# BMWifi.net
KiCad netlist of a schematic drawn in EAGLE
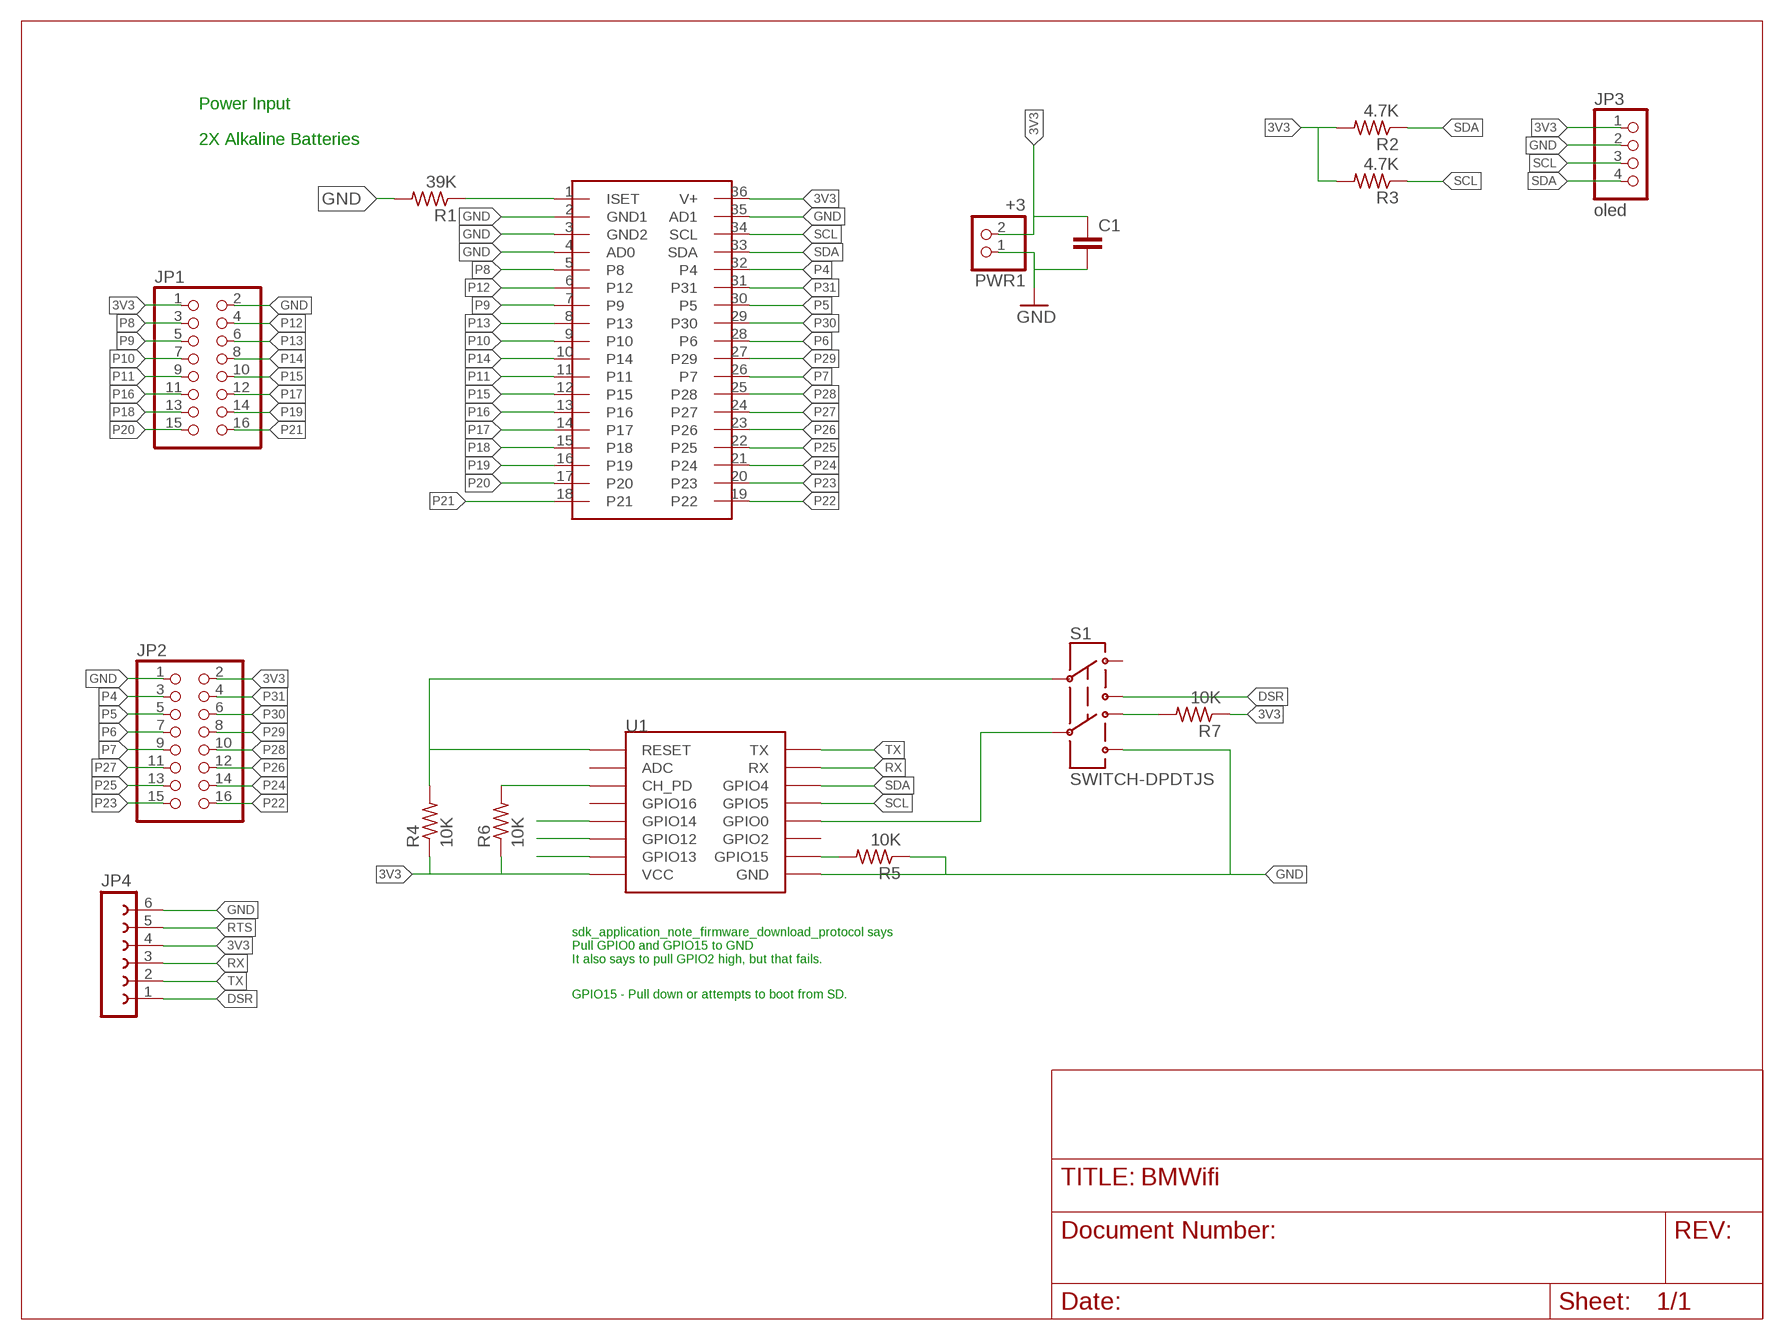
[diagram p0: schematic, sheet 1]

(export (version "E")
  (design (tool "Eeschema 10.0.6"))
  (components
    (comp (ref "C1")
      (value "C2.5/2")
      (footprint "eagle-import:C2.5-2")
      (libsource (lib "eagle-import") (part "C2.5/2"))
    )
    (comp (ref "JP1")
      (value "PINHD-2X8")
      (footprint "eagle-import:2X08")
      (libsource (lib "eagle-import") (part "PINHD-2X8"))
    )
    (comp (ref "JP2")
      (value "PINHD-2X8")
      (footprint "eagle-import:2X08")
      (libsource (lib "eagle-import") (part "PINHD-2X8"))
    )
    (comp (ref "JP3")
      (value "oled")
      (footprint "eagle-import:1X04")
      (libsource (lib "eagle-import") (part "PINHD-1X4"))
    )
    (comp (ref "JP4")
      (value "FE06W")
      (footprint "eagle-import:FE06W")
      (libsource (lib "eagle-import") (part "FE06W"))
    )
    (comp (ref "PWR1")
      (value "+3")
      (footprint "eagle-import:1X02")
      (libsource (lib "eagle-import") (part "PINHD-1X2"))
    )
    (comp (ref "R1")
      (value "39K")
      (footprint "eagle-import:M1206")
      (libsource (lib "eagle-import") (part "R-US_M1206"))
    )
    (comp (ref "R2")
      (value "4.7K")
      (footprint "eagle-import:M1206")
      (libsource (lib "eagle-import") (part "R-US_M1206"))
    )
    (comp (ref "R3")
      (value "4.7K")
      (footprint "eagle-import:M1206")
      (libsource (lib "eagle-import") (part "R-US_M1206"))
    )
    (comp (ref "R4")
      (value "10K")
      (footprint "eagle-import:M1206")
      (libsource (lib "eagle-import") (part "R-US_M1206"))
    )
    (comp (ref "R5")
      (value "10K")
      (footprint "eagle-import:M1206")
      (libsource (lib "eagle-import") (part "R-US_M1206"))
    )
    (comp (ref "R6")
      (value "10K")
      (footprint "eagle-import:M1206")
      (libsource (lib "eagle-import") (part "R-US_M1206"))
    )
    (comp (ref "R7")
      (value "10K")
      (footprint "eagle-import:M1206")
      (libsource (lib "eagle-import") (part "R-US_M1206"))
    )
    (comp (ref "S1")
      (value "SWITCH-DPDTJS")
      (footprint "eagle-import:JS202011CQN")
      (libsource (lib "eagle-import") (part "SWITCH-DPDTJS"))
    )
    (comp (ref "U$1")
      (value "MAX6956")
      (footprint "eagle-import:SSOP36")
      (libsource (lib "eagle-import") (part "MAX6956"))
    )
    (comp (ref "U1")
      (value "ESP12")
      (footprint "eagle-import:ESP12")
      (libsource (lib "eagle-import") (part "ESP12"))
    )
  )
  (nets
    (net (code "1") (name "3V3") (class "Default")
      (node (ref "C1") (pin "1") (pinfunction "1_1") (pintype "passive"))
      (node (ref "JP1") (pin "1") (pinfunction "1_1") (pintype "passive"))
      (node (ref "JP2") (pin "2") (pinfunction "2_2") (pintype "passive"))
      (node (ref "JP3") (pin "1") (pinfunction "1_1") (pintype "passive"))
      (node (ref "JP4") (pin "4") (pinfunction "4_4") (pintype "passive"))
      (node (ref "PWR1") (pin "2") (pinfunction "2_2") (pintype "passive"))
      (node (ref "R2") (pin "2") (pinfunction "2_2") (pintype "passive"))
      (node (ref "R3") (pin "2") (pinfunction "2_2") (pintype "passive"))
      (node (ref "R4") (pin "1") (pinfunction "1_1") (pintype "passive"))
      (node (ref "R6") (pin "1") (pinfunction "1_1") (pintype "passive"))
      (node (ref "R7") (pin "1") (pinfunction "1_1") (pintype "passive"))
      (node (ref "U$1") (pin "36") (pinfunction "V+_36") (pintype "power_in"))
      (node (ref "U1") (pin "VCC") (pinfunction "VCC_VCC") (pintype "bidirectional"))
    )
    (net (code "2") (name "DSR") (class "Default")
      (node (ref "JP4") (pin "1") (pinfunction "1_1") (pintype "passive"))
      (node (ref "S1") (pin "3") (pinfunction "3_3") (pintype "bidirectional"))
    )
    (net (code "3") (name "GND") (class "Default")
      (node (ref "C1") (pin "2") (pinfunction "2_2") (pintype "passive"))
      (node (ref "JP1") (pin "2") (pinfunction "2_2") (pintype "passive"))
      (node (ref "JP2") (pin "1") (pinfunction "1_1") (pintype "passive"))
      (node (ref "JP3") (pin "2") (pinfunction "2_2") (pintype "passive"))
      (node (ref "JP4") (pin "6") (pinfunction "6_6") (pintype "passive"))
      (node (ref "PWR1") (pin "1") (pinfunction "1_1") (pintype "passive"))
      (node (ref "R1") (pin "2") (pinfunction "2_2") (pintype "passive"))
      (node (ref "R5") (pin "1") (pinfunction "1_1") (pintype "passive"))
      (node (ref "S1") (pin "6") (pinfunction "6_6") (pintype "bidirectional"))
      (node (ref "U$1") (pin "2") (pinfunction "GND1_2") (pintype "bidirectional"))
      (node (ref "U$1") (pin "3") (pinfunction "GND2_3") (pintype "bidirectional"))
      (node (ref "U$1") (pin "35") (pinfunction "AD1_35") (pintype "output"))
      (node (ref "U$1") (pin "4") (pinfunction "AD0_4") (pintype "output"))
      (node (ref "U1") (pin "GND") (pinfunction "GND_GND") (pintype "bidirectional"))
    )
    (net (code "4") (name "Net-(R4-Pad2)") (class "Default")
      (node (ref "R4") (pin "2") (pinfunction "2_2") (pintype "passive"))
      (node (ref "S1") (pin "2") (pinfunction "2_2") (pintype "bidirectional"))
      (node (ref "U1") (pin "RESET") (pinfunction "RESET_RESET") (pintype "bidirectional"))
    )
    (net (code "5") (name "Net-(R5-Pad2)") (class "Default")
      (node (ref "R5") (pin "2") (pinfunction "2_2") (pintype "passive"))
      (node (ref "U1") (pin "GPIO15") (pinfunction "GPIO15_GPIO15") (pintype "bidirectional"))
    )
    (net (code "6") (name "Net-(R6-Pad2)") (class "Default")
      (node (ref "R6") (pin "2") (pinfunction "2_2") (pintype "passive"))
      (node (ref "U1") (pin "CH_PD") (pinfunction "CH_PD_CH_PD") (pintype "bidirectional"))
    )
    (net (code "7") (name "Net-(R7-Pad2)") (class "Default")
      (node (ref "R7") (pin "2") (pinfunction "2_2") (pintype "passive"))
      (node (ref "S1") (pin "4") (pinfunction "4_4") (pintype "bidirectional"))
    )
    (net (code "8") (name "Net-(S1-Pad5)") (class "Default")
      (node (ref "S1") (pin "5") (pinfunction "5_5") (pintype "bidirectional"))
      (node (ref "U1") (pin "GPIO0") (pinfunction "GPIO0_GPIO0") (pintype "bidirectional"))
    )
    (net (code "9") (name "Net-(U$1-ISET)") (class "Default")
      (node (ref "R1") (pin "1") (pinfunction "1_1") (pintype "passive"))
      (node (ref "U$1") (pin "1") (pinfunction "ISET_1") (pintype "output"))
    )
    (net (code "10") (name "P4") (class "Default")
      (node (ref "JP2") (pin "3") (pinfunction "3_3") (pintype "passive"))
      (node (ref "U$1") (pin "32") (pinfunction "P4_32") (pintype "bidirectional"))
    )
    (net (code "11") (name "P5") (class "Default")
      (node (ref "JP2") (pin "5") (pinfunction "5_5") (pintype "passive"))
      (node (ref "U$1") (pin "30") (pinfunction "P5_30") (pintype "bidirectional"))
    )
    (net (code "12") (name "P6") (class "Default")
      (node (ref "JP2") (pin "7") (pinfunction "7_7") (pintype "passive"))
      (node (ref "U$1") (pin "28") (pinfunction "P6_28") (pintype "bidirectional"))
    )
    (net (code "13") (name "P7") (class "Default")
      (node (ref "JP2") (pin "9") (pinfunction "9_9") (pintype "passive"))
      (node (ref "U$1") (pin "26") (pinfunction "P7_26") (pintype "bidirectional"))
    )
    (net (code "14") (name "P8") (class "Default")
      (node (ref "JP1") (pin "3") (pinfunction "3_3") (pintype "passive"))
      (node (ref "U$1") (pin "5") (pinfunction "P8_5") (pintype "bidirectional"))
    )
    (net (code "15") (name "P9") (class "Default")
      (node (ref "JP1") (pin "5") (pinfunction "5_5") (pintype "passive"))
      (node (ref "U$1") (pin "7") (pinfunction "P9_7") (pintype "bidirectional"))
    )
    (net (code "16") (name "P10") (class "Default")
      (node (ref "JP1") (pin "7") (pinfunction "7_7") (pintype "passive"))
      (node (ref "U$1") (pin "9") (pinfunction "P10_9") (pintype "bidirectional"))
    )
    (net (code "17") (name "P11") (class "Default")
      (node (ref "JP1") (pin "9") (pinfunction "9_9") (pintype "passive"))
      (node (ref "U$1") (pin "11") (pinfunction "P11_11") (pintype "bidirectional"))
    )
    (net (code "18") (name "P12") (class "Default")
      (node (ref "JP1") (pin "4") (pinfunction "4_4") (pintype "passive"))
      (node (ref "U$1") (pin "6") (pinfunction "P12_6") (pintype "bidirectional"))
    )
    (net (code "19") (name "P13") (class "Default")
      (node (ref "JP1") (pin "6") (pinfunction "6_6") (pintype "passive"))
      (node (ref "U$1") (pin "8") (pinfunction "P13_8") (pintype "bidirectional"))
    )
    (net (code "20") (name "P14") (class "Default")
      (node (ref "JP1") (pin "8") (pinfunction "8_8") (pintype "passive"))
      (node (ref "U$1") (pin "10") (pinfunction "P14_10") (pintype "bidirectional"))
    )
    (net (code "21") (name "P15") (class "Default")
      (node (ref "JP1") (pin "10") (pinfunction "10_10") (pintype "passive"))
      (node (ref "U$1") (pin "12") (pinfunction "P15_12") (pintype "bidirectional"))
    )
    (net (code "22") (name "P16") (class "Default")
      (node (ref "JP1") (pin "11") (pinfunction "11_11") (pintype "passive"))
      (node (ref "U$1") (pin "13") (pinfunction "P16_13") (pintype "bidirectional"))
    )
    (net (code "23") (name "P17") (class "Default")
      (node (ref "JP1") (pin "12") (pinfunction "12_12") (pintype "passive"))
      (node (ref "U$1") (pin "14") (pinfunction "P17_14") (pintype "bidirectional"))
    )
    (net (code "24") (name "P18") (class "Default")
      (node (ref "JP1") (pin "13") (pinfunction "13_13") (pintype "passive"))
      (node (ref "U$1") (pin "15") (pinfunction "P18_15") (pintype "bidirectional"))
    )
    (net (code "25") (name "P19") (class "Default")
      (node (ref "JP1") (pin "14") (pinfunction "14_14") (pintype "passive"))
      (node (ref "U$1") (pin "16") (pinfunction "P19_16") (pintype "bidirectional"))
    )
    (net (code "26") (name "P20") (class "Default")
      (node (ref "JP1") (pin "15") (pinfunction "15_15") (pintype "passive"))
      (node (ref "U$1") (pin "17") (pinfunction "P20_17") (pintype "bidirectional"))
    )
    (net (code "27") (name "P21") (class "Default")
      (node (ref "JP1") (pin "16") (pinfunction "16_16") (pintype "passive"))
      (node (ref "U$1") (pin "18") (pinfunction "P21_18") (pintype "bidirectional"))
    )
    (net (code "28") (name "P22") (class "Default")
      (node (ref "JP2") (pin "16") (pinfunction "16_16") (pintype "passive"))
      (node (ref "U$1") (pin "19") (pinfunction "P22_19") (pintype "bidirectional"))
    )
    (net (code "29") (name "P23") (class "Default")
      (node (ref "JP2") (pin "15") (pinfunction "15_15") (pintype "passive"))
      (node (ref "U$1") (pin "20") (pinfunction "P23_20") (pintype "bidirectional"))
    )
    (net (code "30") (name "P24") (class "Default")
      (node (ref "JP2") (pin "14") (pinfunction "14_14") (pintype "passive"))
      (node (ref "U$1") (pin "21") (pinfunction "P24_21") (pintype "bidirectional"))
    )
    (net (code "31") (name "P25") (class "Default")
      (node (ref "JP2") (pin "13") (pinfunction "13_13") (pintype "passive"))
      (node (ref "U$1") (pin "22") (pinfunction "P25_22") (pintype "bidirectional"))
    )
    (net (code "32") (name "P26") (class "Default")
      (node (ref "JP2") (pin "12") (pinfunction "12_12") (pintype "passive"))
      (node (ref "U$1") (pin "23") (pinfunction "P26_23") (pintype "bidirectional"))
    )
    (net (code "33") (name "P27") (class "Default")
      (node (ref "JP2") (pin "11") (pinfunction "11_11") (pintype "passive"))
      (node (ref "U$1") (pin "24") (pinfunction "P27_24") (pintype "bidirectional"))
    )
    (net (code "34") (name "P28") (class "Default")
      (node (ref "JP2") (pin "10") (pinfunction "10_10") (pintype "passive"))
      (node (ref "U$1") (pin "25") (pinfunction "P28_25") (pintype "bidirectional"))
    )
    (net (code "35") (name "P29") (class "Default")
      (node (ref "JP2") (pin "8") (pinfunction "8_8") (pintype "passive"))
      (node (ref "U$1") (pin "27") (pinfunction "P29_27") (pintype "bidirectional"))
    )
    (net (code "36") (name "P30") (class "Default")
      (node (ref "JP2") (pin "6") (pinfunction "6_6") (pintype "passive"))
      (node (ref "U$1") (pin "29") (pinfunction "P30_29") (pintype "bidirectional"))
    )
    (net (code "37") (name "P31") (class "Default")
      (node (ref "JP2") (pin "4") (pinfunction "4_4") (pintype "passive"))
      (node (ref "U$1") (pin "31") (pinfunction "P31_31") (pintype "bidirectional"))
    )
    (net (code "38") (name "RTS") (class "Default")
      (node (ref "JP4") (pin "5") (pinfunction "5_5") (pintype "passive"))
    )
    (net (code "39") (name "RX") (class "Default")
      (node (ref "JP4") (pin "3") (pinfunction "3_3") (pintype "passive"))
      (node (ref "U1") (pin "RX") (pinfunction "RX_RX") (pintype "bidirectional"))
    )
    (net (code "40") (name "SCL") (class "Default")
      (node (ref "JP3") (pin "3") (pinfunction "3_3") (pintype "passive"))
      (node (ref "R3") (pin "1") (pinfunction "1_1") (pintype "passive"))
      (node (ref "U$1") (pin "34") (pinfunction "SCL_34") (pintype "bidirectional"))
      (node (ref "U1") (pin "GPIO5") (pinfunction "GPIO5_GPIO5") (pintype "bidirectional"))
    )
    (net (code "41") (name "SDA") (class "Default")
      (node (ref "JP3") (pin "4") (pinfunction "4_4") (pintype "passive"))
      (node (ref "R2") (pin "1") (pinfunction "1_1") (pintype "passive"))
      (node (ref "U$1") (pin "33") (pinfunction "SDA_33") (pintype "bidirectional"))
      (node (ref "U1") (pin "GPIO4") (pinfunction "GPIO4_GPIO4") (pintype "bidirectional"))
    )
    (net (code "42") (name "TX") (class "Default")
      (node (ref "JP4") (pin "2") (pinfunction "2_2") (pintype "passive"))
      (node (ref "U1") (pin "TX") (pinfunction "TX_TX") (pintype "bidirectional"))
    )
    (net (code "43") (name "unconnected-(S1-Pad1)") (class "Default")
      (node (ref "S1") (pin "1") (pinfunction "1_1") (pintype "bidirectional"))
    )
    (net (code "44") (name "unconnected-(U1-PadADC)") (class "Default")
      (node (ref "U1") (pin "ADC") (pinfunction "ADC_ADC") (pintype "bidirectional"))
    )
    (net (code "45") (name "unconnected-(U1-PadGPIO2)") (class "Default")
      (node (ref "U1") (pin "GPIO2") (pinfunction "GPIO2_GPIO2") (pintype "bidirectional"))
    )
    (net (code "46") (name "unconnected-(U1-PadGPIO12)") (class "Default")
      (node (ref "U1") (pin "GPIO12") (pinfunction "GPIO12_GPIO12") (pintype "bidirectional"))
    )
    (net (code "47") (name "unconnected-(U1-PadGPIO13)") (class "Default")
      (node (ref "U1") (pin "GPIO13") (pinfunction "GPIO13_GPIO13") (pintype "bidirectional"))
    )
    (net (code "48") (name "unconnected-(U1-PadGPIO14)") (class "Default")
      (node (ref "U1") (pin "GPIO14") (pinfunction "GPIO14_GPIO14") (pintype "bidirectional"))
    )
    (net (code "49") (name "unconnected-(U1-PadGPIO16)") (class "Default")
      (node (ref "U1") (pin "GPIO16") (pinfunction "GPIO16_GPIO16") (pintype "bidirectional"))
    )
  )
)
